# MCUModule.net
KiCad netlist of a schematic drawn in Altium Designer
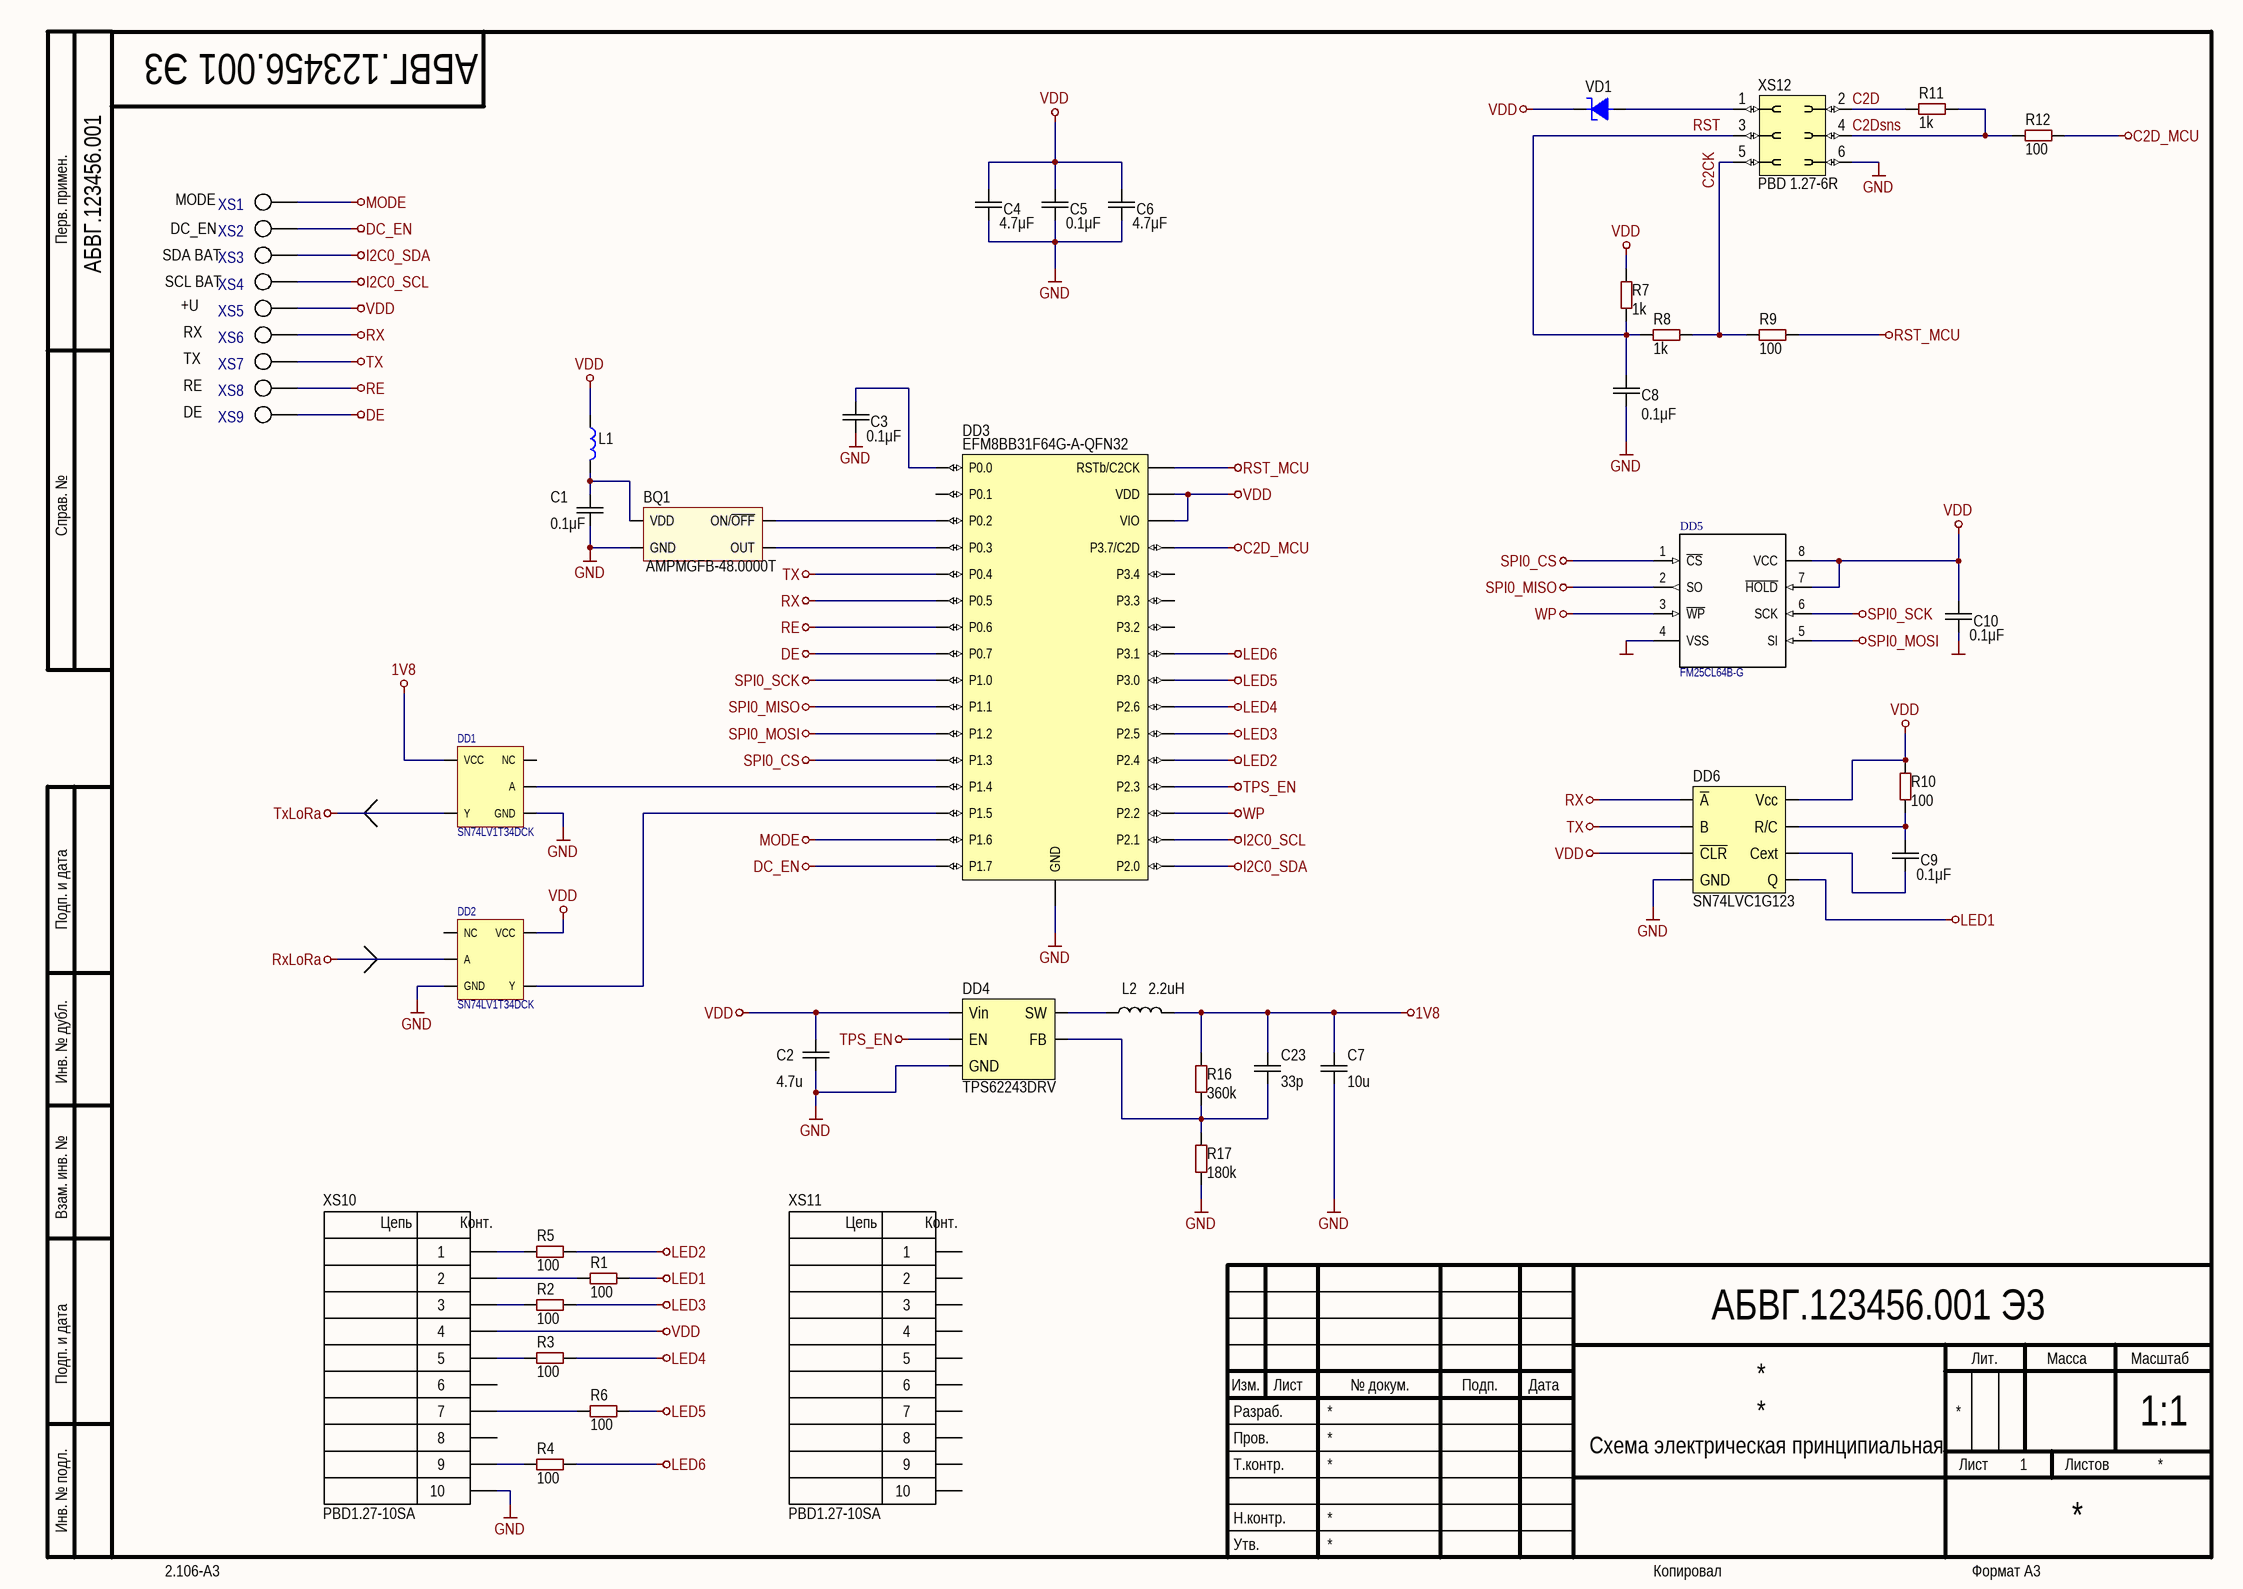
[diagram p0: MCUModule.SchDoc]

(export (version "E")
  (design (tool "Eeschema 10.0.6"))
  (components
    (comp (ref "BQ1")
      (value "AMPMGFB-48.0000T")
      (footprint "AMPMGFB(1.6x1.2)")
      (libsource (lib "oscilator") (part "AMPMGFB-48.0000T"))
    )
    (comp (ref "C1")
      (value "0.1μF")
      (footprint "CAP: 0603")
      (fields
        (field (name "MANUFACTURER") "Yageo")
        (field (name "PARTNUMBER") "CC0603KRX7R7BB104")
        (field (name "VALUEMANUFACTURERPARTNUMBER") "Ceramic capacitor, 0.1μF, X7R, ±10%, 16V, 0603, -55...+125°C")
      )
      (libsource (lib "capacitor") (part "Ceramic_0603"))
    )
    (comp (ref "C2")
      (value "4.7u")
      (footprint "CAP: 0603")
      (fields
        (field (name "MANUFACTURER") "Yageo")
        (field (name "PARTNUMBER") "CC0603KRX7R7BB104")
        (field (name "VALUEMANUFACTURERPARTNUMBER") "Ceramic capacitor, 4.7u, X7R, ±10%, 16V, 0603, -55...+125°C")
      )
      (libsource (lib "capacitor") (part "Ceramic_0603"))
    )
    (comp (ref "C3")
      (value "0.1μF")
      (footprint "CAP: 0603")
      (fields
        (field (name "MANUFACTURER") "Yageo")
        (field (name "PARTNUMBER") "CC0603KRX7R7BB104")
        (field (name "VALUEMANUFACTURERPARTNUMBER") "Ceramic capacitor, 0.1μF, X7R, ±10%, 16V, 0603, -55...+125°C")
      )
      (libsource (lib "capacitor") (part "Ceramic_0603"))
    )
    (comp (ref "C4")
      (value "4.7μF")
      (footprint "CAP: 0603")
      (fields
        (field (name "MANUFACTURER") "Yageo")
        (field (name "PARTNUMBER") "CC0603KRX7R7BB104")
        (field (name "VALUEMANUFACTURERPARTNUMBER") "Ceramic capacitor, 4.7μF, X7R, ±10%, 16V, 0603, -55...+125°C")
      )
      (libsource (lib "capacitor") (part "Ceramic_0603"))
    )
    (comp (ref "C5")
      (value "0.1μF")
      (footprint "CAP: 0603")
      (fields
        (field (name "MANUFACTURER") "Yageo")
        (field (name "PARTNUMBER") "CC0603KRX7R7BB104")
        (field (name "VALUEMANUFACTURERPARTNUMBER") "Ceramic capacitor, 0.1μF, X7R, ±10%, 16V, 0603, -55...+125°C")
      )
      (libsource (lib "capacitor") (part "Ceramic_0603"))
    )
    (comp (ref "C6")
      (value "4.7μF")
      (footprint "CAP: 0603")
      (fields
        (field (name "MANUFACTURER") "Yageo")
        (field (name "PARTNUMBER") "CC0603KRX7R7BB104")
        (field (name "VALUEMANUFACTURERPARTNUMBER") "Ceramic capacitor, 4.7μF, X7R, ±10%, 16V, 0603, -55...+125°C")
      )
      (libsource (lib "capacitor") (part "Ceramic_0603"))
    )
    (comp (ref "C7")
      (value "10u")
      (footprint "CAP: 0603")
      (fields
        (field (name "MANUFACTURER") "Yageo")
        (field (name "PARTNUMBER") "CC0603KRX7R7BB104")
        (field (name "VALUEMANUFACTURERPARTNUMBER") "Ceramic capacitor, 10u, X7R, ±10%, 16V, 0603, -55...+125°C")
      )
      (libsource (lib "capacitor") (part "Ceramic_0603"))
    )
    (comp (ref "C8")
      (value "0.1μF")
      (footprint "CAP: 0603")
      (fields
        (field (name "MANUFACTURER") "Yageo")
        (field (name "PARTNUMBER") "CC0603KRX7R7BB104")
        (field (name "VALUEMANUFACTURERPARTNUMBER") "Ceramic capacitor, 0.1μF, X7R, ±10%, 16V, 0603, -55...+125°C")
      )
      (libsource (lib "capacitor") (part "Ceramic_0603"))
    )
    (comp (ref "C9")
      (value "0.1μF")
      (footprint "CAP: 0603")
      (fields
        (field (name "MANUFACTURER") "Yageo")
        (field (name "PARTNUMBER") "CC0603KRX7R7BB104")
        (field (name "VALUEMANUFACTURERPARTNUMBER") "Ceramic capacitor, 0.1μF, X7R, ±10%, 16V, 0603, -55...+125°C")
      )
      (libsource (lib "capacitor") (part "Ceramic_0603"))
    )
    (comp (ref "C10")
      (value "0.1μF")
      (footprint "CAP: 0603")
      (fields
        (field (name "MANUFACTURER") "Yageo")
        (field (name "PARTNUMBER") "CC0603KRX7R7BB104")
        (field (name "VALUEMANUFACTURERPARTNUMBER") "Ceramic capacitor, 0.1μF, X7R, ±10%, 16V, 0603, -55...+125°C")
      )
      (libsource (lib "capacitor") (part "Ceramic_0603"))
    )
    (comp (ref "C23")
      (value "33p")
      (footprint "CAP: 0603")
      (fields
        (field (name "MANUFACTURER") "Yageo")
        (field (name "PARTNUMBER") "CC0603KRX7R7BB104")
        (field (name "VALUEMANUFACTURERPARTNUMBER") "Ceramic capacitor, 33p, X7R, ±10%, 16V, 0603, -55...+125°C")
      )
      (libsource (lib "capacitor") (part "Ceramic_0603"))
    )
    (comp (ref "DD1")
      (value "SN74LV1T34DCK")
      (footprint "SC70-5")
      (description "Single Buffer")
      (libsource (lib "") (part "SN74LV1T34DCK_1"))
    )
    (comp (ref "DD2")
      (value "SN74LV1T34DCK")
      (footprint "SC70-5")
      (description "Single Buffer")
      (libsource (lib "ic-logic") (part "SN74LV1T34DCK"))
    )
    (comp (ref "DD3")
      (value "EFM8BB31F64G-A-QFN32")
      (footprint "32-QFN(4x4)")
      (description "8051 MCU Core")
      (libsource (lib "ic-mcu") (part "EFM8BB31F64G-A-QFN32"))
    )
    (comp (ref "DD4")
      (value "TPS62243DRV")
      (footprint "SOT23-5")
      (description "Step-down converter 300mA")
      (libsource (lib "ic-power-supply") (part "TPS62243DRV"))
    )
    (comp (ref "DD5")
      (value "FM25CL64B-G")
      (footprint "SO-8_N")
      (description "Микросхема")
      (fields (field (name "REPLACEMENTPART1PARTNUMBER") "IS25C08-2ZLI-TR"))
      (libsource (lib "FRAM") (part "FM25CL64B-G"))
    )
    (comp (ref "DD6")
      (value "SN74LVC1G123")
      (footprint "8-VSSOP")
      (description "Monostable Multivibrator\r\nWith Schmitt-Trigger Inputs")
      (libsource (lib "ic-logic") (part "SN74LVC1G123"))
    )
    (comp (ref "L1")
      (value "BLM18AG102SN1D")
      (footprint "IND: 0603")
      (description "100MHz 1K")
      (libsource (lib "inductor") (part "BLM18AG102SN1D"))
    )
    (comp (ref "L2")
      (value "2.2uH")
      (footprint "VLF302515MT")
      (fields (field (name "Comment") "VLF302515MT"))
      (libsource (lib "inductor") (part "VLF302515MT"))
    )
    (comp (ref "R1")
      (value "100")
      (footprint "RES: 0603")
      (fields
        (field (name "MANUFACTURER") "Yageo")
        (field (name "PARTNUMBER") "RC0603JR-07100RL")
        (field (name "VALUEMANUFACTURERPARTNUMBER") "Resistor film, 100, ±5%, 0603, 0.1W, -55...+125°C")
      )
      (libsource (lib "resistor") (part "Resistor_0603"))
    )
    (comp (ref "R2")
      (value "100")
      (footprint "RES: 0603")
      (fields
        (field (name "MANUFACTURER") "Yageo")
        (field (name "PARTNUMBER") "RC0603JR-07100RL")
        (field (name "VALUEMANUFACTURERPARTNUMBER") "Resistor film, 100, ±5%, 0603, 0.1W, -55...+125°C")
      )
      (libsource (lib "resistor") (part "Resistor_0603"))
    )
    (comp (ref "R3")
      (value "100")
      (footprint "RES: 0603")
      (fields
        (field (name "MANUFACTURER") "Yageo")
        (field (name "PARTNUMBER") "RC0603JR-07100RL")
        (field (name "VALUEMANUFACTURERPARTNUMBER") "Resistor film, 100, ±5%, 0603, 0.1W, -55...+125°C")
      )
      (libsource (lib "resistor") (part "Resistor_0603"))
    )
    (comp (ref "R4")
      (value "100")
      (footprint "RES: 0603")
      (fields
        (field (name "MANUFACTURER") "Yageo")
        (field (name "PARTNUMBER") "RC0603JR-07100RL")
        (field (name "VALUEMANUFACTURERPARTNUMBER") "Resistor film, 100, ±5%, 0603, 0.1W, -55...+125°C")
      )
      (libsource (lib "resistor") (part "Resistor_0603"))
    )
    (comp (ref "R5")
      (value "100")
      (footprint "RES: 0603")
      (fields
        (field (name "MANUFACTURER") "Yageo")
        (field (name "PARTNUMBER") "RC0603JR-07100RL")
        (field (name "VALUEMANUFACTURERPARTNUMBER") "Resistor film, 100, ±5%, 0603, 0.1W, -55...+125°C")
      )
      (libsource (lib "resistor") (part "Resistor_0603"))
    )
    (comp (ref "R6")
      (value "100")
      (footprint "RES: 0603")
      (fields
        (field (name "MANUFACTURER") "Yageo")
        (field (name "PARTNUMBER") "RC0603JR-07100RL")
        (field (name "VALUEMANUFACTURERPARTNUMBER") "Resistor film, 100, ±5%, 0603, 0.1W, -55...+125°C")
      )
      (libsource (lib "resistor") (part "Resistor_0603"))
    )
    (comp (ref "R7")
      (value "1k")
      (footprint "RES: 0603")
      (fields
        (field (name "MANUFACTURER") "Yageo")
        (field (name "PARTNUMBER") "RC0603JR-07100RL")
        (field (name "VALUEMANUFACTURERPARTNUMBER") "Resistor film, 1k, ±5%, 0603, 0.1W, -55...+125°C")
      )
      (libsource (lib "") (part "Resistor_0603_1"))
    )
    (comp (ref "R8")
      (value "1k")
      (footprint "RES: 0603")
      (fields
        (field (name "MANUFACTURER") "Yageo")
        (field (name "PARTNUMBER") "RC0603JR-07100RL")
        (field (name "VALUEMANUFACTURERPARTNUMBER") "Resistor film, 1k, ±5%, 0603, 0.1W, -55...+125°C")
      )
      (libsource (lib "resistor") (part "Resistor_0603"))
    )
    (comp (ref "R9")
      (value "100")
      (footprint "RES: 0603")
      (fields
        (field (name "MANUFACTURER") "Yageo")
        (field (name "PARTNUMBER") "RC0603JR-07100RL")
        (field (name "VALUEMANUFACTURERPARTNUMBER") "Resistor film, 100, ±5%, 0603, 0.1W, -55...+125°C")
      )
      (libsource (lib "resistor") (part "Resistor_0603"))
    )
    (comp (ref "R10")
      (value "100")
      (footprint "RES: 0603")
      (fields
        (field (name "MANUFACTURER") "Yageo")
        (field (name "PARTNUMBER") "RC0603JR-07100RL")
        (field (name "VALUEMANUFACTURERPARTNUMBER") "Resistor film, 100, ±5%, 0603, 0.1W, -55...+125°C")
      )
      (libsource (lib "") (part "Resistor_0603_1"))
    )
    (comp (ref "R11")
      (value "1k")
      (footprint "RES: 0603")
      (fields
        (field (name "MANUFACTURER") "Yageo")
        (field (name "PARTNUMBER") "RC0603JR-07100RL")
        (field (name "VALUEMANUFACTURERPARTNUMBER") "Resistor film, 1k, ±5%, 0603, 0.1W, -55...+125°C")
      )
      (libsource (lib "resistor") (part "Resistor_0603"))
    )
    (comp (ref "R12")
      (value "100")
      (footprint "RES: 0603")
      (fields
        (field (name "MANUFACTURER") "Yageo")
        (field (name "PARTNUMBER") "RC0603JR-07100RL")
        (field (name "VALUEMANUFACTURERPARTNUMBER") "Resistor film, 100, ±5%, 0603, 0.1W, -55...+125°C")
      )
      (libsource (lib "") (part "Resistor_0603_1"))
    )
    (comp (ref "R16")
      (value "360k")
      (footprint "RES: 0603")
      (fields
        (field (name "MANUFACTURER") "Yageo")
        (field (name "PARTNUMBER") "RC0603JR-07100RL")
        (field (name "VALUEMANUFACTURERPARTNUMBER") "Resistor film, 360k, ±5%, 0603, 0.1W, -55...+125°C")
      )
      (libsource (lib "") (part "Resistor_0603_1"))
    )
    (comp (ref "R17")
      (value "180k")
      (footprint "RES: 0603")
      (fields
        (field (name "MANUFACTURER") "Yageo")
        (field (name "PARTNUMBER") "RC0603JR-07100RL")
        (field (name "VALUEMANUFACTURERPARTNUMBER") "Resistor film, 180k, ±5%, 0603, 0.1W, -55...+125°C")
      )
      (libsource (lib "") (part "Resistor_0603_1"))
    )
    (comp (ref "VD1")
      (value "~")
      (footprint "DIODE: SOD523")
      (fields
        (field (name "MANUFACTURER") "Diodes Incorporated")
        (field (name "VALUEMANUFACTURERPARTNUMBER") "Schottky diode, 80V, 500mA, 1V, 15pF, SOD-123, -55...+150°C")
        (field (name "VOLTAGE") "80V")
      )
      (libsource (lib "diode") (part "Schottky_single"))
    )
    (comp (ref "XS1")
      (value "Testpoint_HS1mm")
      (footprint "TestPoint(without 3D)")
      (libsource (lib "connector") (part "Testpoint_HS1mm"))
    )
    (comp (ref "XS2")
      (value "Testpoint_HS1mm")
      (footprint "TestPoint(without 3D)")
      (libsource (lib "connector") (part "Testpoint_HS1mm"))
    )
    (comp (ref "XS3")
      (value "Testpoint_HS1mm")
      (footprint "TestPoint(without 3D)")
      (libsource (lib "connector") (part "Testpoint_HS1mm"))
    )
    (comp (ref "XS4")
      (value "Testpoint_HS1mm")
      (footprint "TestPoint(without 3D)")
      (libsource (lib "connector") (part "Testpoint_HS1mm"))
    )
    (comp (ref "XS5")
      (value "Testpoint_HS1mm")
      (footprint "TestPoint(without 3D)")
      (libsource (lib "connector") (part "Testpoint_HS1mm"))
    )
    (comp (ref "XS6")
      (value "Testpoint_HS1mm")
      (footprint "TestPoint(without 3D)")
      (libsource (lib "connector") (part "Testpoint_HS1mm"))
    )
    (comp (ref "XS7")
      (value "Testpoint_HS1mm")
      (footprint "TestPoint(without 3D)")
      (libsource (lib "connector") (part "Testpoint_HS1mm"))
    )
    (comp (ref "XS8")
      (value "Testpoint_HS1mm")
      (footprint "TestPoint(without 3D)")
      (libsource (lib "connector") (part "Testpoint_HS1mm"))
    )
    (comp (ref "XS9")
      (value "Testpoint_HS1mm")
      (footprint "TestPoint(without 3D)")
      (libsource (lib "connector") (part "Testpoint_HS1mm"))
    )
    (comp (ref "XS10")
      (value "PBD1.27-10SA")
      (footprint "CON: PBD-10-1.27S")
      (libsource (lib "connector") (part "PBD1.27-10SA"))
    )
    (comp (ref "XS11")
      (value "PBD1.27-10SA")
      (footprint "CON: PBD-10-1.27S")
      (libsource (lib "connector") (part "PBD1.27-10SA"))
    )
    (comp (ref "XS12")
      (value "PBD 1.27-6R")
      (footprint "CON: PBD1.27-6")
      (libsource (lib "connector") (part "PBD 1.27-6R"))
    )
  )
  (nets
    (net (code "1") (name "/C2CK") (class "Default")
      (node (ref "R8") (pin "2") (pinfunction "2_2") (pintype "passive"))
      (node (ref "R9") (pin "1") (pinfunction "1_1") (pintype "passive"))
      (node (ref "XS12") (pin "5") (pinfunction "5_5") (pintype "bidirectional"))
    )
    (net (code "2") (name "/C2D") (class "Default")
      (node (ref "R11") (pin "1") (pinfunction "1_1") (pintype "passive"))
      (node (ref "XS12") (pin "2") (pinfunction "2_2") (pintype "bidirectional"))
    )
    (net (code "3") (name "/C2Dsns") (class "Default")
      (node (ref "R11") (pin "2") (pinfunction "2_2") (pintype "passive"))
      (node (ref "R12") (pin "2") (pinfunction "2_2") (pintype "passive"))
      (node (ref "XS12") (pin "4") (pinfunction "4_4") (pintype "bidirectional"))
    )
    (net (code "4") (name "/RST") (class "Default")
      (node (ref "C8") (pin "2") (pinfunction "2_2") (pintype "passive"))
      (node (ref "R7") (pin "2") (pinfunction "2_2") (pintype "passive"))
      (node (ref "R8") (pin "1") (pinfunction "1_1") (pintype "passive"))
      (node (ref "XS12") (pin "3") (pinfunction "3_3") (pintype "bidirectional"))
    )
    (net (code "5") (name "1V8") (class "Default")
      (node (ref "C23") (pin "2") (pinfunction "2_2") (pintype "passive"))
      (node (ref "C7") (pin "2") (pinfunction "2_2") (pintype "passive"))
      (node (ref "DD1") (pin "5") (pinfunction "VCC_5") (pintype "passive"))
      (node (ref "L2") (pin "2") (pinfunction "2_2") (pintype "passive"))
      (node (ref "R16") (pin "1") (pinfunction "1_1") (pintype "passive"))
    )
    (net (code "6") (name "C2D_MCU") (class "Default")
      (node (ref "DD3") (pin "5") (pinfunction "P3.7/C2D_5") (pintype "bidirectional"))
      (node (ref "R12") (pin "1") (pinfunction "1_1") (pintype "passive"))
    )
    (net (code "7") (name "DC_EN") (class "Default")
      (node (ref "DD3") (pin "18") (pinfunction "P1.7_18") (pintype "bidirectional"))
      (node (ref "XS2") (pin "1") (pinfunction "1_1") (pintype "passive"))
    )
    (net (code "8") (name "DE") (class "Default")
      (node (ref "DD3") (pin "26") (pinfunction "P0.7_26") (pintype "bidirectional"))
      (node (ref "XS9") (pin "1") (pinfunction "1_1") (pintype "passive"))
    )
    (net (code "9") (name "GND") (class "Default")
      (node (ref "BQ1") (pin "2") (pinfunction "GND_2") (pintype "passive"))
      (node (ref "C1") (pin "1") (pinfunction "1_1") (pintype "passive"))
      (node (ref "C10") (pin "1") (pinfunction "1_1") (pintype "passive"))
      (node (ref "C2") (pin "1") (pinfunction "1_1") (pintype "passive"))
      (node (ref "C3") (pin "1") (pinfunction "1_1") (pintype "passive"))
      (node (ref "C4") (pin "1") (pinfunction "1_1") (pintype "passive"))
      (node (ref "C5") (pin "1") (pinfunction "1_1") (pintype "passive"))
      (node (ref "C6") (pin "1") (pinfunction "1_1") (pintype "passive"))
      (node (ref "C7") (pin "1") (pinfunction "1_1") (pintype "passive"))
      (node (ref "C8") (pin "1") (pinfunction "1_1") (pintype "passive"))
      (node (ref "DD1") (pin "3") (pinfunction "GND_3") (pintype "passive"))
      (node (ref "DD2") (pin "3") (pinfunction "GND_3") (pintype "passive"))
      (node (ref "DD3") (pin "0") (pinfunction "GND_0") (pintype "passive"))
      (node (ref "DD4") (pin "2") (pinfunction "GND_2") (pintype "passive"))
      (node (ref "DD5") (pin "4") (pinfunction "VSS_4") (pintype "power_in"))
      (node (ref "DD6") (pin "4") (pinfunction "GND_4") (pintype "passive"))
      (node (ref "R17") (pin "2") (pinfunction "2_2") (pintype "passive"))
      (node (ref "XS10") (pin "10") (pinfunction "10_10") (pintype "power_in"))
      (node (ref "XS12") (pin "6") (pinfunction "6_6") (pintype "bidirectional"))
    )
    (net (code "10") (name "I2C0_SCL") (class "Default")
      (node (ref "DD3") (pin "16") (pinfunction "P2.1_16") (pintype "bidirectional"))
      (node (ref "XS4") (pin "1") (pinfunction "1_1") (pintype "passive"))
    )
    (net (code "11") (name "I2C0_SDA") (class "Default")
      (node (ref "DD3") (pin "17") (pinfunction "P2.0_17") (pintype "bidirectional"))
      (node (ref "XS3") (pin "1") (pinfunction "1_1") (pintype "passive"))
    )
    (net (code "12") (name "LED1") (class "Default")
      (node (ref "DD6") (pin "5") (pinfunction "Q_5") (pintype "passive"))
      (node (ref "R1") (pin "2") (pinfunction "2_2") (pintype "passive"))
    )
    (net (code "13") (name "LED2") (class "Default")
      (node (ref "DD3") (pin "13") (pinfunction "P2.4_13") (pintype "bidirectional"))
      (node (ref "R5") (pin "2") (pinfunction "2_2") (pintype "passive"))
    )
    (net (code "14") (name "LED3") (class "Default")
      (node (ref "DD3") (pin "12") (pinfunction "P2.5_12") (pintype "bidirectional"))
      (node (ref "R2") (pin "2") (pinfunction "2_2") (pintype "passive"))
    )
    (net (code "15") (name "LED4") (class "Default")
      (node (ref "DD3") (pin "11") (pinfunction "P2.6_11") (pintype "bidirectional"))
      (node (ref "R3") (pin "2") (pinfunction "2_2") (pintype "passive"))
    )
    (net (code "16") (name "LED5") (class "Default")
      (node (ref "DD3") (pin "10") (pinfunction "P3.0_10") (pintype "bidirectional"))
      (node (ref "R6") (pin "2") (pinfunction "2_2") (pintype "passive"))
    )
    (net (code "17") (name "LED6") (class "Default")
      (node (ref "DD3") (pin "9") (pinfunction "P3.1_9") (pintype "bidirectional"))
      (node (ref "R4") (pin "2") (pinfunction "2_2") (pintype "passive"))
    )
    (net (code "18") (name "MODE") (class "Default")
      (node (ref "DD3") (pin "19") (pinfunction "P1.6_19") (pintype "bidirectional"))
      (node (ref "XS1") (pin "1") (pinfunction "1_1") (pintype "passive"))
    )
    (net (code "19") (name "Net-(BQ1-ON{slash}~{OFF})") (class "Default")
      (node (ref "BQ1") (pin "1") (pinfunction "ON/~{OFF}_1") (pintype "passive"))
      (node (ref "DD3") (pin "31") (pinfunction "P0.2_31") (pintype "bidirectional"))
    )
    (net (code "20") (name "Net-(BQ1-OUT)") (class "Default")
      (node (ref "BQ1") (pin "3") (pinfunction "OUT_3") (pintype "passive"))
      (node (ref "DD3") (pin "30") (pinfunction "P0.3_30") (pintype "bidirectional"))
    )
    (net (code "21") (name "Net-(BQ1-VDD)") (class "Default")
      (node (ref "BQ1") (pin "4") (pinfunction "VDD_4") (pintype "passive"))
      (node (ref "C1") (pin "2") (pinfunction "2_2") (pintype "passive"))
      (node (ref "L1") (pin "2") (pinfunction "2_2") (pintype "passive"))
    )
    (net (code "22") (name "Net-(DD1-A)") (class "Default")
      (node (ref "DD1") (pin "2") (pinfunction "A_2") (pintype "passive"))
      (node (ref "DD3") (pin "21") (pinfunction "P1.4_21") (pintype "bidirectional"))
    )
    (net (code "23") (name "Net-(DD2-Y)") (class "Default")
      (node (ref "DD2") (pin "4") (pinfunction "Y_4") (pintype "passive"))
      (node (ref "DD3") (pin "20") (pinfunction "P1.5_20") (pintype "bidirectional"))
    )
    (net (code "24") (name "Net-(DD3-P0.0)") (class "Default")
      (node (ref "C3") (pin "2") (pinfunction "2_2") (pintype "passive"))
      (node (ref "DD3") (pin "1") (pinfunction "P0.0_1") (pintype "bidirectional"))
    )
    (net (code "25") (name "Net-(DD4-FB)") (class "Default")
      (node (ref "C23") (pin "1") (pinfunction "1_1") (pintype "passive"))
      (node (ref "DD4") (pin "4") (pinfunction "FB_4") (pintype "passive"))
      (node (ref "R16") (pin "2") (pinfunction "2_2") (pintype "passive"))
      (node (ref "R17") (pin "1") (pinfunction "1_1") (pintype "passive"))
    )
    (net (code "26") (name "Net-(DD4-SW)") (class "Default")
      (node (ref "DD4") (pin "5") (pinfunction "SW_5") (pintype "passive"))
      (node (ref "L2") (pin "1") (pinfunction "1_1") (pintype "passive"))
    )
    (net (code "27") (name "Net-(DD6-Cext)") (class "Default")
      (node (ref "C9") (pin "1") (pinfunction "1_1") (pintype "passive"))
      (node (ref "DD6") (pin "6") (pinfunction "Cext_6") (pintype "passive"))
    )
    (net (code "28") (name "Net-(DD6-R{slash}C)") (class "Default")
      (node (ref "C9") (pin "2") (pinfunction "2_2") (pintype "passive"))
      (node (ref "DD6") (pin "7") (pinfunction "R/C_7") (pintype "passive"))
      (node (ref "R10") (pin "2") (pinfunction "2_2") (pintype "passive"))
    )
    (net (code "29") (name "Net-(R1-Pad1)") (class "Default")
      (node (ref "R1") (pin "1") (pinfunction "1_1") (pintype "passive"))
      (node (ref "XS10") (pin "2") (pinfunction "2_2") (pintype "passive"))
    )
    (net (code "30") (name "Net-(R2-Pad1)") (class "Default")
      (node (ref "R2") (pin "1") (pinfunction "1_1") (pintype "passive"))
      (node (ref "XS10") (pin "3") (pinfunction "3_3") (pintype "power_in"))
    )
    (net (code "31") (name "Net-(R3-Pad1)") (class "Default")
      (node (ref "R3") (pin "1") (pinfunction "1_1") (pintype "passive"))
      (node (ref "XS10") (pin "5") (pinfunction "5_5") (pintype "power_in"))
    )
    (net (code "32") (name "Net-(R4-Pad1)") (class "Default")
      (node (ref "R4") (pin "1") (pinfunction "1_1") (pintype "passive"))
      (node (ref "XS10") (pin "9") (pinfunction "9_9") (pintype "power_in"))
    )
    (net (code "33") (name "Net-(R5-Pad1)") (class "Default")
      (node (ref "R5") (pin "1") (pinfunction "1_1") (pintype "passive"))
      (node (ref "XS10") (pin "1") (pinfunction "1_1") (pintype "passive"))
    )
    (net (code "34") (name "Net-(R6-Pad1)") (class "Default")
      (node (ref "R6") (pin "1") (pinfunction "1_1") (pintype "passive"))
      (node (ref "XS10") (pin "7") (pinfunction "7_7") (pintype "power_in"))
    )
    (net (code "35") (name "Net-(VD1-Pad1)") (class "Default")
      (node (ref "VD1") (pin "1") (pinfunction "1_1") (pintype "passive"))
      (node (ref "XS12") (pin "1") (pinfunction "1_1") (pintype "bidirectional"))
    )
    (net (code "36") (name "RE") (class "Default")
      (node (ref "DD3") (pin "27") (pinfunction "P0.6_27") (pintype "bidirectional"))
      (node (ref "XS8") (pin "1") (pinfunction "1_1") (pintype "passive"))
    )
    (net (code "37") (name "RST_MCU") (class "Default")
      (node (ref "DD3") (pin "4") (pinfunction "RSTb/C2CK_4") (pintype "passive"))
      (node (ref "R9") (pin "2") (pinfunction "2_2") (pintype "passive"))
    )
    (net (code "38") (name "RX") (class "Default")
      (node (ref "DD3") (pin "28") (pinfunction "P0.5_28") (pintype "bidirectional"))
      (node (ref "DD6") (pin "1") (pinfunction "~{A}_1") (pintype "passive"))
      (node (ref "XS6") (pin "1") (pinfunction "1_1") (pintype "passive"))
    )
    (net (code "39") (name "RxLoRa") (class "Default")
      (node (ref "DD2") (pin "2") (pinfunction "A_2") (pintype "passive"))
    )
    (net (code "40") (name "SPI0_CS") (class "Default")
      (node (ref "DD3") (pin "22") (pinfunction "P1.3_22") (pintype "bidirectional"))
      (node (ref "DD5") (pin "1") (pinfunction "~{CS}_1") (pintype "input"))
    )
    (net (code "41") (name "SPI0_MISO") (class "Default")
      (node (ref "DD3") (pin "24") (pinfunction "P1.1_24") (pintype "bidirectional"))
      (node (ref "DD5") (pin "2") (pinfunction "SO_2") (pintype "output"))
    )
    (net (code "42") (name "SPI0_MOSI") (class "Default")
      (node (ref "DD3") (pin "23") (pinfunction "P1.2_23") (pintype "bidirectional"))
      (node (ref "DD5") (pin "5") (pinfunction "SI_5") (pintype "input"))
    )
    (net (code "43") (name "SPI0_SCK") (class "Default")
      (node (ref "DD3") (pin "25") (pinfunction "P1.0_25") (pintype "bidirectional"))
      (node (ref "DD5") (pin "6") (pinfunction "SCK_6") (pintype "input"))
    )
    (net (code "44") (name "TPS_EN") (class "Default")
      (node (ref "DD3") (pin "14") (pinfunction "P2.3_14") (pintype "bidirectional"))
      (node (ref "DD4") (pin "3") (pinfunction "EN_3") (pintype "passive"))
    )
    (net (code "45") (name "TX") (class "Default")
      (node (ref "DD3") (pin "29") (pinfunction "P0.4_29") (pintype "bidirectional"))
      (node (ref "DD6") (pin "2") (pinfunction "B_2") (pintype "passive"))
      (node (ref "XS7") (pin "1") (pinfunction "1_1") (pintype "passive"))
    )
    (net (code "46") (name "TxLoRa") (class "Default")
      (node (ref "DD1") (pin "4") (pinfunction "Y_4") (pintype "passive"))
    )
    (net (code "47") (name "VDD") (class "Default")
      (node (ref "C10") (pin "2") (pinfunction "2_2") (pintype "passive"))
      (node (ref "C2") (pin "2") (pinfunction "2_2") (pintype "passive"))
      (node (ref "C4") (pin "2") (pinfunction "2_2") (pintype "passive"))
      (node (ref "C5") (pin "2") (pinfunction "2_2") (pintype "passive"))
      (node (ref "C6") (pin "2") (pinfunction "2_2") (pintype "passive"))
      (node (ref "DD2") (pin "5") (pinfunction "VCC_5") (pintype "passive"))
      (node (ref "DD3") (pin "2") (pinfunction "VIO_2") (pintype "passive"))
      (node (ref "DD3") (pin "3") (pinfunction "VDD_3") (pintype "passive"))
      (node (ref "DD4") (pin "1") (pinfunction "Vin_1") (pintype "passive"))
      (node (ref "DD5") (pin "7") (pinfunction "~{HOLD}_7") (pintype "input"))
      (node (ref "DD5") (pin "8") (pinfunction "VCC_8") (pintype "power_in"))
      (node (ref "DD6") (pin "3") (pinfunction "~{CLR}_3") (pintype "passive"))
      (node (ref "DD6") (pin "8") (pinfunction "Vcc_8") (pintype "passive"))
      (node (ref "L1") (pin "1") (pinfunction "1_1") (pintype "passive"))
      (node (ref "R10") (pin "1") (pinfunction "1_1") (pintype "passive"))
      (node (ref "R7") (pin "1") (pinfunction "1_1") (pintype "passive"))
      (node (ref "VD1") (pin "2") (pinfunction "2_2") (pintype "passive"))
      (node (ref "XS10") (pin "4") (pinfunction "4_4") (pintype "power_in"))
      (node (ref "XS5") (pin "1") (pinfunction "1_1") (pintype "passive"))
    )
    (net (code "48") (name "WP") (class "Default")
      (node (ref "DD3") (pin "15") (pinfunction "P2.2_15") (pintype "bidirectional"))
      (node (ref "DD5") (pin "3") (pinfunction "~{WP}_3") (pintype "input"))
    )
    (net (code "49") (name "unconnected-(DD1-NC-Pad1)") (class "Default")
      (node (ref "DD1") (pin "1") (pinfunction "NC_1") (pintype "passive"))
    )
    (net (code "50") (name "unconnected-(DD2-NC-Pad1)") (class "Default")
      (node (ref "DD2") (pin "1") (pinfunction "NC_1") (pintype "passive"))
    )
    (net (code "51") (name "unconnected-(DD3-P0.1-Pad32)") (class "Default")
      (node (ref "DD3") (pin "32") (pinfunction "P0.1_32") (pintype "bidirectional"))
    )
    (net (code "52") (name "unconnected-(DD3-P3.2-Pad8)") (class "Default")
      (node (ref "DD3") (pin "8") (pinfunction "P3.2_8") (pintype "bidirectional"))
    )
    (net (code "53") (name "unconnected-(DD3-P3.3-Pad7)") (class "Default")
      (node (ref "DD3") (pin "7") (pinfunction "P3.3_7") (pintype "bidirectional"))
    )
    (net (code "54") (name "unconnected-(DD3-P3.4-Pad6)") (class "Default")
      (node (ref "DD3") (pin "6") (pinfunction "P3.4_6") (pintype "bidirectional"))
    )
    (net (code "55") (name "unconnected-(XS10-Pad6)") (class "Default")
      (node (ref "XS10") (pin "6") (pinfunction "6_6") (pintype "power_in"))
    )
    (net (code "56") (name "unconnected-(XS10-Pad8)") (class "Default")
      (node (ref "XS10") (pin "8") (pinfunction "8_8") (pintype "power_in"))
    )
    (net (code "57") (name "unconnected-(XS11-Pad1)") (class "Default")
      (node (ref "XS11") (pin "1") (pinfunction "1_1") (pintype "passive"))
    )
    (net (code "58") (name "unconnected-(XS11-Pad2)") (class "Default")
      (node (ref "XS11") (pin "2") (pinfunction "2_2") (pintype "passive"))
    )
    (net (code "59") (name "unconnected-(XS11-Pad3)") (class "Default")
      (node (ref "XS11") (pin "3") (pinfunction "3_3") (pintype "power_in"))
    )
    (net (code "60") (name "unconnected-(XS11-Pad4)") (class "Default")
      (node (ref "XS11") (pin "4") (pinfunction "4_4") (pintype "power_in"))
    )
    (net (code "61") (name "unconnected-(XS11-Pad5)") (class "Default")
      (node (ref "XS11") (pin "5") (pinfunction "5_5") (pintype "power_in"))
    )
    (net (code "62") (name "unconnected-(XS11-Pad6)") (class "Default")
      (node (ref "XS11") (pin "6") (pinfunction "6_6") (pintype "power_in"))
    )
    (net (code "63") (name "unconnected-(XS11-Pad7)") (class "Default")
      (node (ref "XS11") (pin "7") (pinfunction "7_7") (pintype "power_in"))
    )
    (net (code "64") (name "unconnected-(XS11-Pad8)") (class "Default")
      (node (ref "XS11") (pin "8") (pinfunction "8_8") (pintype "power_in"))
    )
    (net (code "65") (name "unconnected-(XS11-Pad9)") (class "Default")
      (node (ref "XS11") (pin "9") (pinfunction "9_9") (pintype "power_in"))
    )
    (net (code "66") (name "unconnected-(XS11-Pad10)") (class "Default")
      (node (ref "XS11") (pin "10") (pinfunction "10_10") (pintype "power_in"))
    )
  )
)
